# morse_code_watch.net
KiCad netlist of a schematic drawn in Altium Designer
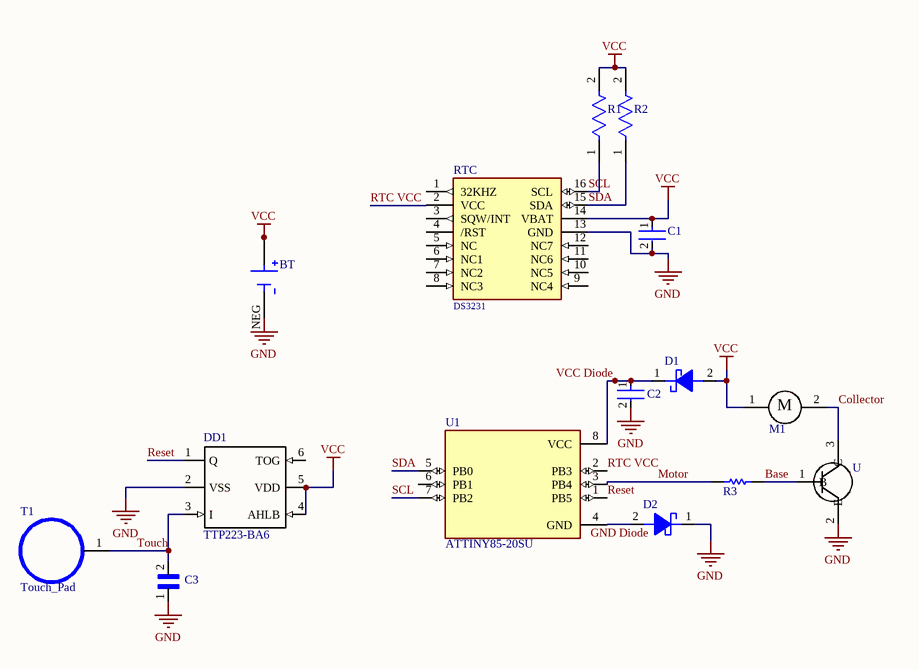
[diagram p0: morse_code_watch.SchDoc]

(export (version "E")
  (design (tool "Eeschema 10.0.6"))
  (components
    (comp (ref "BT")
      (value "BC-2005")
      (footprint "BAT_BC-2005")
      (description "Battery Retainer Coin, 24.0mm 1 Cell SMD _SMT_ Tab")
      (fields (field (name "MF") "MPD _Memory Protection Devices_") (field (name "MP") "BC-2005-TR"))
      (libsource (lib "BC-2005") (part "BC-2005"))
    )
    (comp (ref "C1")
      (value "C3216C0G1H104J160AA")
      (footprint "FP-C3216-160-0_2-IPC_B")
      (description "Multilayer Ceramic Capacitors 100nF ±5% 50V C0G SMD 1206")
      (fields (field (name "TOLERANCE") "5%"))
      (libsource (lib "Altium Content Vault") (part "11868f565c42a9108669ba33697ecf6"))
    )
    (comp (ref "C2")
      (value "C3216C0G1H104J160AA")
      (footprint "FP-C3216-160-0_2-IPC_B")
      (description "Multilayer Ceramic Capacitors 100nF ±5% 50V C0G SMD 1206")
      (fields (field (name "TOLERANCE") "5%"))
      (libsource (lib "Altium Content Vault") (part "11868f565c42a9108669ba33697ecf6"))
    )
    (comp (ref "C3")
      (value "08051A500GAT2A")
      (footprint "CAPC2012X94N")
      (description "Cap Ceramic 50pF 100V C0G 2% SMD 0805 125Â°C T/R")
      (libsource (lib "08051A500GAT2A") (part "08051A500GAT2A"))
    )
    (comp (ref "D1")
      (value "PMEG1020EA")
      (footprint "PMEG1020EA")
      (libsource (lib "morse_code_watch") (part "PMEG1020EA"))
    )
    (comp (ref "D2")
      (value "PMEG1020EA")
      (footprint "PMEG1020EA")
      (libsource (lib "morse_code_watch") (part "PMEG1020EA"))
    )
    (comp (ref "DD1")
      (value "TTP223-BA6")
      (footprint "SOT23-6")
      (description "1 KEY TOUCH PAD DETECTOR IC")
      (libsource (lib "TTP223-BA6") (part "TTP223-BA6"))
    )
    (comp (ref "M1")
      (value "VZ4TL2B0620044P")
      (footprint "VZ4TL2B0620044P")
      (libsource (lib "morse_code_watch") (part "VZ4TL2B0620044P"))
    )
    (comp (ref "R1")
      (value "RNCP0805FTD10K0")
      (footprint "FP-RNCP0805-IPC_C")
      (description "10kΩ ±1% 0.25W 0805 High Power Anti-Sulfur Thin Film Chip Resistor")
      (fields (field (name "TOLERANCE") "1%"))
      (libsource (lib "Altium Content Vault") (part "1029c3af85768c4190bb7ad29bc67b5"))
    )
    (comp (ref "R2")
      (value "RNCP0805FTD10K0")
      (footprint "FP-RNCP0805-IPC_C")
      (description "10kΩ ±1% 0.25W 0805 High Power Anti-Sulfur Thin Film Chip Resistor")
      (fields (field (name "TOLERANCE") "1%"))
      (libsource (lib "Altium Content Vault") (part "1029c3af85768c4190bb7ad29bc67b5"))
    )
    (comp (ref "R3")
      (value "ERA6AEB122V")
      (footprint "RESC2013X60X40LL20T25")
      (fields (field (name "MANUFACTURER") "Panasonic"))
      (libsource (lib "Altium Content Vault") (part "RES"))
    )
    (comp (ref "RTC")
      (value "~")
      (footprint "SO16W")
      (fields (field (name "MP") "DS3231") (field (name "MF") "Maxim Integrated"))
      (libsource (lib "DS3231") (part "DS3231"))
    )
    (comp (ref "T1") (value "Touch_Pad") (libsource (lib "morse_code_watch") (part "Touch_Pad")))
    (comp (ref "U")
      (value "BC847BT-7-F")
      (footprint "SOT50P160X90-3N")
      (description "Bipolar _BJT_ Transistor NPN 45V 100mA 100MHz 150mW Surface Mount SOT-523")
      (fields (field (name "MF") "Diodes Inc."))
      (libsource (lib "BC847BT-7-F") (part "BC847BT-7-F"))
    )
    (comp (ref "U1")
      (value "ATTINY85-20SU")
      (footprint "SOIC127P798X216-8N")
      (fields (field (name "MF") "Microchip"))
      (libsource (lib "ATTINY85-20SU") (part "ATTINY85-20SU"))
    )
  )
  (nets
    (net (code "1") (name "/Base") (class "Default")
      (node (ref "R3") (pin "2") (pinfunction "2_2") (pintype "passive"))
      (node (ref "U") (pin "1") (pinfunction "B_1") (pintype "passive"))
    )
    (net (code "2") (name "/Collector") (class "Default")
      (node (ref "M1") (pin "2") (pinfunction "2_2") (pintype "passive"))
      (node (ref "U") (pin "3") (pinfunction "C_3") (pintype "passive"))
    )
    (net (code "3") (name "/GND Diode") (class "Default")
      (node (ref "D2") (pin "2") (pintype "passive"))
      (node (ref "U1") (pin "4") (pinfunction "GND_4") (pintype "power_in"))
    )
    (net (code "4") (name "/Motor") (class "Default")
      (node (ref "R3") (pin "1") (pinfunction "1_1") (pintype "passive"))
      (node (ref "U1") (pin "3") (pinfunction "PB4_3") (pintype "bidirectional"))
    )
    (net (code "5") (name "/RTC VCC") (class "Default")
      (node (ref "RTC") (pin "2") (pinfunction "VCC_2") (pintype "power_in"))
      (node (ref "U1") (pin "2") (pinfunction "PB3_2") (pintype "bidirectional"))
    )
    (net (code "6") (name "/Reset") (class "Default")
      (node (ref "DD1") (pin "1") (pinfunction "Q_1") (pintype "power_in"))
      (node (ref "U1") (pin "1") (pinfunction "PB5_1") (pintype "bidirectional"))
    )
    (net (code "7") (name "/SCL") (class "Default")
      (node (ref "R1") (pin "1") (pinfunction "1_1") (pintype "passive"))
      (node (ref "RTC") (pin "16") (pinfunction "SCL_16") (pintype "bidirectional"))
      (node (ref "U1") (pin "7") (pinfunction "PB2_7") (pintype "bidirectional"))
    )
    (net (code "8") (name "/SDA") (class "Default")
      (node (ref "R2") (pin "1") (pinfunction "1_1") (pintype "passive"))
      (node (ref "RTC") (pin "15") (pinfunction "SDA_15") (pintype "bidirectional"))
      (node (ref "U1") (pin "5") (pinfunction "PB0_5") (pintype "bidirectional"))
    )
    (net (code "9") (name "/Touch") (class "Default")
      (node (ref "C3") (pin "2") (pinfunction "2_2") (pintype "passive"))
      (node (ref "DD1") (pin "3") (pinfunction "I_3") (pintype "input"))
      (node (ref "T1") (pin "1") (pinfunction "1_1") (pintype "passive"))
    )
    (net (code "10") (name "/VCC Diode") (class "Default")
      (node (ref "C2") (pin "1") (pinfunction "1_1") (pintype "passive"))
      (node (ref "D1") (pin "1") (pintype "passive"))
      (node (ref "U1") (pin "8") (pinfunction "VCC_8") (pintype "power_in"))
    )
    (net (code "11") (name "GND") (class "Default")
      (node (ref "BT") (pin "NEG") (pinfunction "NEG_NEG") (pintype "passive"))
      (node (ref "C1") (pin "2") (pinfunction "2_2") (pintype "passive"))
      (node (ref "C2") (pin "2") (pinfunction "2_2") (pintype "passive"))
      (node (ref "C3") (pin "1") (pinfunction "1_1") (pintype "passive"))
      (node (ref "D2") (pin "1") (pintype "passive"))
      (node (ref "DD1") (pin "2") (pinfunction "VSS_2") (pintype "power_in"))
      (node (ref "RTC") (pin "13") (pinfunction "GND_13") (pintype "power_in"))
      (node (ref "U") (pin "2") (pinfunction "E_2") (pintype "passive"))
    )
    (net (code "12") (name "VCC") (class "Default")
      (node (ref "BT") (pin "S1+") (pinfunction "POS_S1+") (pintype "passive"))
      (node (ref "BT") (pin "S2+") (pinfunction "POS_S2+") (pintype "passive"))
      (node (ref "C1") (pin "1") (pinfunction "1_1") (pintype "passive"))
      (node (ref "D1") (pin "2") (pintype "passive"))
      (node (ref "DD1") (pin "4") (pinfunction "AHLB_4") (pintype "input"))
      (node (ref "DD1") (pin "5") (pinfunction "VDD_5") (pintype "power_in"))
      (node (ref "M1") (pin "1") (pinfunction "1_1") (pintype "passive"))
      (node (ref "R1") (pin "2") (pinfunction "2_2") (pintype "passive"))
      (node (ref "R2") (pin "2") (pinfunction "2_2") (pintype "passive"))
      (node (ref "RTC") (pin "14") (pinfunction "VBAT_14") (pintype "power_in"))
    )
    (net (code "13") (name "unconnected-(DD1-TOG-Pad6)") (class "Default")
      (node (ref "DD1") (pin "6") (pinfunction "TOG_6") (pintype "input"))
    )
    (net (code "14") (name "unconnected-(RTC-32KHZ-Pad1)") (class "Default")
      (node (ref "RTC") (pin "1") (pinfunction "32KHZ_1") (pintype "output"))
    )
    (net (code "15") (name "unconnected-(RTC-NC-Pad5)") (class "Default")
      (node (ref "RTC") (pin "5") (pinfunction "NC_5") (pintype "input"))
    )
    (net (code "16") (name "unconnected-(RTC-NC1-Pad6)") (class "Default")
      (node (ref "RTC") (pin "6") (pinfunction "NC1_6") (pintype "input"))
    )
    (net (code "17") (name "unconnected-(RTC-NC2-Pad7)") (class "Default")
      (node (ref "RTC") (pin "7") (pinfunction "NC2_7") (pintype "input"))
    )
    (net (code "18") (name "unconnected-(RTC-NC3-Pad8)") (class "Default")
      (node (ref "RTC") (pin "8") (pinfunction "NC3_8") (pintype "input"))
    )
    (net (code "19") (name "unconnected-(RTC-NC4-Pad9)") (class "Default")
      (node (ref "RTC") (pin "9") (pinfunction "NC4_9") (pintype "input"))
    )
    (net (code "20") (name "unconnected-(RTC-NC5-Pad10)") (class "Default")
      (node (ref "RTC") (pin "10") (pinfunction "NC5_10") (pintype "input"))
    )
    (net (code "21") (name "unconnected-(RTC-NC6-Pad11)") (class "Default")
      (node (ref "RTC") (pin "11") (pinfunction "NC6_11") (pintype "input"))
    )
    (net (code "22") (name "unconnected-(RTC-NC7-Pad12)") (class "Default")
      (node (ref "RTC") (pin "12") (pinfunction "NC7_12") (pintype "input"))
    )
    (net (code "23") (name "unconnected-(RTC-SQW{slash}INT-Pad3)") (class "Default")
      (node (ref "RTC") (pin "3") (pinfunction "SQW/INT_3") (pintype "output"))
    )
    (net (code "24") (name "unconnected-(RTC-{slash}RST-Pad4)") (class "Default")
      (node (ref "RTC") (pin "4") (pinfunction "/RST_4") (pintype "passive"))
    )
    (net (code "25") (name "unconnected-(U1-PB1-Pad6)") (class "Default")
      (node (ref "U1") (pin "6") (pinfunction "PB1_6") (pintype "bidirectional"))
    )
  )
)
